# design.net
KiCad netlist of a schematic drawn in EasyEDA Pro
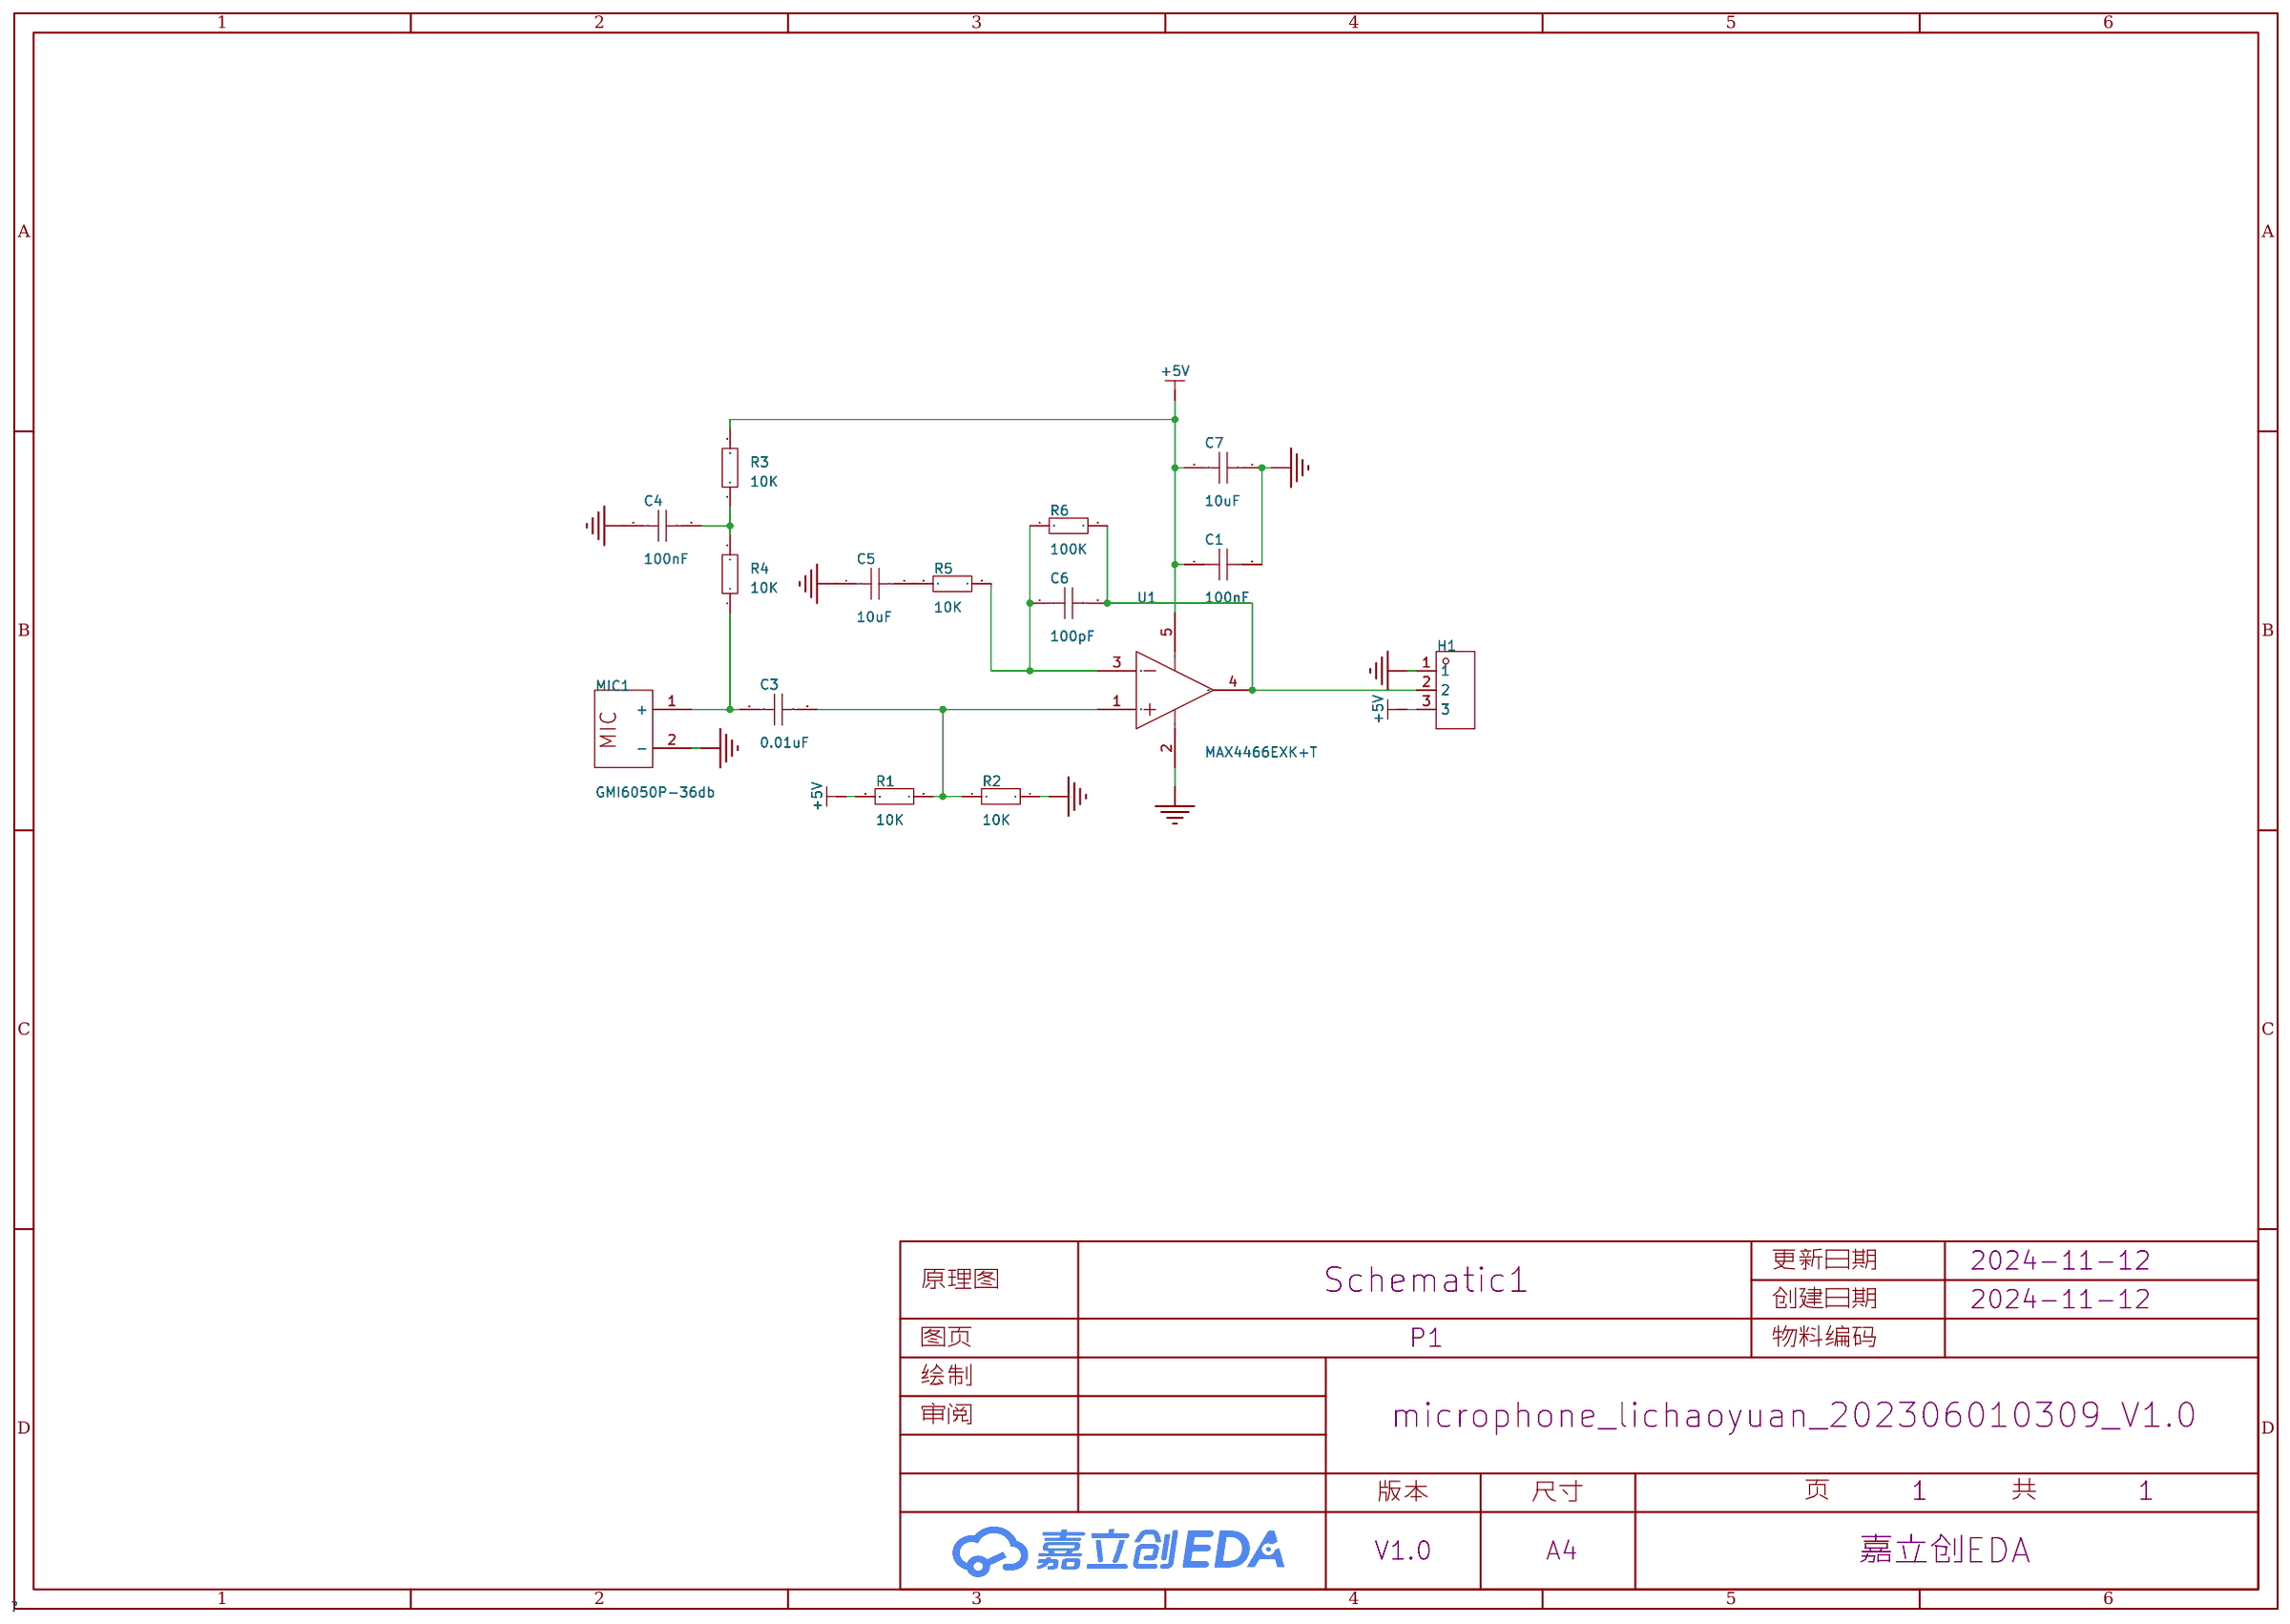
[diagram p0: schematic sheet]

(export (version "E")
  (design (tool "Eeschema 10.0.6"))
  (components
    (comp (ref "C1")
      (value "100nF")
      (footprint "easyedapro:C0603")
      (libsource (lib "easyedapro") (part "CapAcitance"))
    )
    (comp (ref "C3")
      (value "0.01uF")
      (footprint "easyedapro:C0603")
      (libsource (lib "easyedapro") (part "CapAcitance"))
    )
    (comp (ref "C4")
      (value "100nF")
      (footprint "easyedapro:C0603")
      (libsource (lib "easyedapro") (part "CapAcitance"))
    )
    (comp (ref "C5")
      (value "10uF")
      (footprint "easyedapro:C0603")
      (libsource (lib "easyedapro") (part "CapAcitance"))
    )
    (comp (ref "C6")
      (value "100pF")
      (footprint "easyedapro:C0603")
      (libsource (lib "easyedapro") (part "CapAcitance"))
    )
    (comp (ref "C7")
      (value "10uF")
      (footprint "easyedapro:C0603")
      (libsource (lib "easyedapro") (part "CapAcitance"))
    )
    (comp (ref "H1")
      (value "~")
      (footprint "easyedapro:HDR-TH_3P-P2.54-V-F")
      (libsource (lib "easyedapro") (part "PM254V-11-03-H85"))
    )
    (comp (ref "MIC1")
      (value "GMI6050P-36db")
      (footprint "easyedapro:MIC-TH_BD6.0-P1.90-D0.4-L-FD_GMI6050P-2CXXDB")
      (fields (field (name "Manufacturer") "INGHAi(赢海)"))
      (libsource (lib "easyedapro") (part "GMI6050P-36DB"))
    )
    (comp (ref "R1") (value "10K") (footprint "easyedapro:R0603") (libsource (lib "easyedapro") (part "电阻")))
    (comp (ref "R2") (value "10K") (footprint "easyedapro:R0603") (libsource (lib "easyedapro") (part "电阻")))
    (comp (ref "R3") (value "10K") (footprint "easyedapro:R0603") (libsource (lib "easyedapro") (part "电阻")))
    (comp (ref "R4") (value "10K") (footprint "easyedapro:R0603") (libsource (lib "easyedapro") (part "电阻")))
    (comp (ref "R5") (value "10K") (footprint "easyedapro:R0603") (libsource (lib "easyedapro") (part "电阻")))
    (comp (ref "R6") (value "100K") (footprint "easyedapro:R0603") (libsource (lib "easyedapro") (part "电阻")))
    (comp (ref "U1")
      (value "MAX4466EXK+T")
      (footprint "easyedapro:SC-70-5_L2.0-W1.3-P0.65-LS2.1-BR")
      (description "功放类型:-;扬声器通道数:单声道;输出功率:-;静态电流(Iq):-;")
      (fields (field (name "Manufacturer") "ADI(亚德诺)/MAXIM(美信)"))
      (libsource (lib "easyedapro") (part "MAX4466EXK+T"))
    )
  )
  (nets
    (net (code "1") (name "+5V") (class "Default")
      (node (ref "C1") (pin "1") (pinfunction "1_1") (pintype "input"))
      (node (ref "C7") (pin "2") (pinfunction "2_2") (pintype "input"))
      (node (ref "H1") (pin "3") (pinfunction "3_3") (pintype "unspecified"))
      (node (ref "R1") (pin "2") (pinfunction "2_2") (pintype "input"))
      (node (ref "R3") (pin "2") (pinfunction "2_2") (pintype "input"))
      (node (ref "U1") (pin "5") (pinfunction "VCC_5") (pintype "unspecified"))
    )
    (net (code "2") (name "GND") (class "Default")
      (node (ref "C1") (pin "2") (pinfunction "2_2") (pintype "input"))
      (node (ref "C4") (pin "1") (pinfunction "1_1") (pintype "input"))
      (node (ref "C5") (pin "1") (pinfunction "1_1") (pintype "input"))
      (node (ref "C7") (pin "1") (pinfunction "1_1") (pintype "input"))
      (node (ref "H1") (pin "1") (pinfunction "1_1") (pintype "unspecified"))
      (node (ref "MIC1") (pin "2") (pinfunction "-_2") (pintype "unspecified"))
      (node (ref "R2") (pin "1") (pinfunction "1_1") (pintype "input"))
      (node (ref "U1") (pin "2") (pinfunction "GND_2") (pintype "unspecified"))
    )
    (net (code "3") (name "Net-(C4-Pad2)") (class "Default")
      (node (ref "C4") (pin "2") (pinfunction "2_2") (pintype "input"))
      (node (ref "R3") (pin "1") (pinfunction "1_1") (pintype "input"))
      (node (ref "R4") (pin "2") (pinfunction "2_2") (pintype "input"))
    )
    (net (code "4") (name "Net-(C5-Pad2)") (class "Default")
      (node (ref "C5") (pin "2") (pinfunction "2_2") (pintype "input"))
      (node (ref "R5") (pin "1") (pinfunction "1_1") (pintype "input"))
    )
    (net (code "5") (name "Net-(MIC1-+)") (class "Default")
      (node (ref "C3") (pin "1") (pinfunction "1_1") (pintype "input"))
      (node (ref "MIC1") (pin "1") (pinfunction "+_1") (pintype "unspecified"))
      (node (ref "R4") (pin "1") (pinfunction "1_1") (pintype "input"))
    )
    (net (code "6") (name "Net-(U1-IN+)") (class "Default")
      (node (ref "C3") (pin "2") (pinfunction "2_2") (pintype "input"))
      (node (ref "R1") (pin "1") (pinfunction "1_1") (pintype "input"))
      (node (ref "R2") (pin "2") (pinfunction "2_2") (pintype "input"))
      (node (ref "U1") (pin "1") (pinfunction "IN+_1") (pintype "unspecified"))
    )
    (net (code "7") (name "Net-(U1-IN-)") (class "Default")
      (node (ref "C6") (pin "1") (pinfunction "1_1") (pintype "input"))
      (node (ref "R5") (pin "2") (pinfunction "2_2") (pintype "input"))
      (node (ref "R6") (pin "1") (pinfunction "1_1") (pintype "input"))
      (node (ref "U1") (pin "3") (pinfunction "IN-_3") (pintype "unspecified"))
    )
    (net (code "8") (name "Net-(U1-OUT)") (class "Default")
      (node (ref "C6") (pin "2") (pinfunction "2_2") (pintype "input"))
      (node (ref "H1") (pin "2") (pinfunction "2_2") (pintype "unspecified"))
      (node (ref "R6") (pin "2") (pinfunction "2_2") (pintype "input"))
      (node (ref "U1") (pin "4") (pinfunction "OUT_4") (pintype "output"))
    )
  )
)
